# shift_relays.net
KiCad netlist of a schematic drawn in Altium Designer
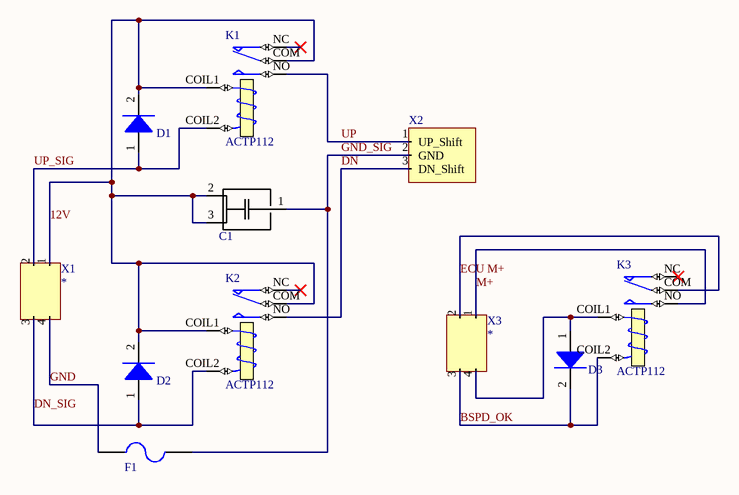
[diagram p0: shift_relays.SchDoc]

(export (version "E")
  (design (tool "Eeschema 10.0.6"))
  (components
    (comp (ref "C1")
      (value "Part Number: BZ05FB682ZSB")
      (footprint "BZX5-S")
      (description "6.8mF (EDLC) Supercapacitor 15V BZ05, 3 Lead")
      (fields
        (field (name "MANUFACTURER_PART_NUMBER") "BZ05FB682ZSB")
        (field (name "VOLTAGE") "15")
        (field (name "COPYRIGHT") "Copyright (C) 2018 Accelerated Designs. All rights reserved")
        (field (name "CREATEDBY") "Patrick Reedy")
      )
      (libsource (lib "altlib") (part "BZ05FB682ZSB"))
    )
    (comp (ref "D1")
      (value "*")
      (footprint "SOD123F")
      (description "Diode Super Barrier 40V 1A Surface Mount SOD-")
      (libsource (lib "altlib") (part "DIODE"))
    )
    (comp (ref "D2")
      (value "*")
      (footprint "SOD123F")
      (description "Diode Super Barrier 40V 1A Surface Mount SOD-")
      (libsource (lib "altlib") (part "DIODE"))
    )
    (comp (ref "D3")
      (value "*")
      (footprint "SOD123F")
      (description "Diode Super Barrier 40V 1A Surface Mount SOD-")
      (libsource (lib "altlib") (part "DIODE"))
    )
    (comp (ref "F1")
      (value "Fuse")
      (footprint "3568-MiniFuseHolder")
      (libsource (lib "altlib") (part "Fuse"))
    )
    (comp (ref "K1")
      (value "ACTP112")
      (footprint "ACTP112")
      (fields
        (field (name "VOLTAGE") "12")
        (field (name "PUBLISHER") "Altium Limited")
        (field (name "CREATEDBY") "Kevin")
      )
      (libsource (lib "altlib") (part "ACTP112"))
    )
    (comp (ref "K2")
      (value "ACTP112")
      (footprint "ACTP112")
      (fields
        (field (name "VOLTAGE") "12")
        (field (name "PUBLISHER") "Altium Limited")
        (field (name "CREATEDBY") "Kevin")
      )
      (libsource (lib "altlib") (part "ACTP112"))
    )
    (comp (ref "K3")
      (value "ACTP112")
      (footprint "ACTP112")
      (fields
        (field (name "VOLTAGE") "12")
        (field (name "PUBLISHER") "Altium Limited")
        (field (name "CREATEDBY") "Kevin")
      )
      (libsource (lib "altlib") (part "ACTP112"))
    )
    (comp (ref "X1")
      (value "*")
      (footprint "DTF13-4P")
      (description "DTF13-4P")
      (libsource (lib "altlib") (part "CONN 4POS"))
    )
    (comp (ref "X2")
      (value "~")
      (footprint "CONN_Shift")
      (description "Connector for Shift Relays")
      (fields (field (name "CREATEDBY") "Patrick"))
      (libsource (lib "altlib") (part "CONN Shift"))
    )
    (comp (ref "X3")
      (value "*")
      (footprint "DTF13-4P")
      (description "DTF13-4P")
      (libsource (lib "altlib") (part "CONN 4POS"))
    )
  )
  (nets
    (net (code "1") (name "/12V") (class "Default")
      (node (ref "C1") (pin "2") (pinfunction "2_2") (pintype "passive"))
      (node (ref "C1") (pin "3") (pinfunction "3_3") (pintype "passive"))
      (node (ref "D1") (pin "2") (pinfunction "K_2") (pintype "passive"))
      (node (ref "D2") (pin "2") (pinfunction "K_2") (pintype "passive"))
      (node (ref "K1") (pin "COIL1") (pinfunction "T1_COIL1") (pintype "bidirectional"))
      (node (ref "K1") (pin "COM") (pinfunction "COM_COM") (pintype "bidirectional"))
      (node (ref "K2") (pin "COIL1") (pinfunction "T1_COIL1") (pintype "bidirectional"))
      (node (ref "K2") (pin "COM") (pinfunction "COM_COM") (pintype "bidirectional"))
      (node (ref "X1") (pin "1") (pintype "input"))
    )
    (net (code "2") (name "/BSPD_OK") (class "Default")
      (node (ref "D3") (pin "2") (pinfunction "K_2") (pintype "passive"))
      (node (ref "K3") (pin "COIL2") (pinfunction "T2_COIL2") (pintype "bidirectional"))
      (node (ref "X3") (pin "3") (pintype "input"))
    )
    (net (code "3") (name "/DN") (class "Default")
      (node (ref "K2") (pin "NO") (pinfunction "NO_NO") (pintype "bidirectional"))
      (node (ref "X2") (pin "3") (pinfunction "DN_Shift_3") (pintype "input"))
    )
    (net (code "4") (name "/DN_SIG") (class "Default")
      (node (ref "D2") (pin "1") (pinfunction "A_1") (pintype "passive"))
      (node (ref "K2") (pin "COIL2") (pinfunction "T2_COIL2") (pintype "bidirectional"))
      (node (ref "X1") (pin "3") (pintype "input"))
    )
    (net (code "5") (name "/ECU M+") (class "Default")
      (node (ref "K3") (pin "COM") (pinfunction "COM_COM") (pintype "bidirectional"))
      (node (ref "X3") (pin "2") (pintype "input"))
    )
    (net (code "6") (name "/GND") (class "Default")
      (node (ref "F1") (pin "1") (pinfunction "1_1") (pintype "passive"))
      (node (ref "X1") (pin "4") (pintype "input"))
    )
    (net (code "7") (name "/GND_SIG") (class "Default")
      (node (ref "C1") (pin "1") (pinfunction "1_1") (pintype "passive"))
      (node (ref "F1") (pin "2") (pinfunction "2_2") (pintype "passive"))
      (node (ref "X2") (pin "2") (pinfunction "GND_2") (pintype "input"))
    )
    (net (code "8") (name "/M+") (class "Default")
      (node (ref "K3") (pin "NO") (pinfunction "NO_NO") (pintype "bidirectional"))
      (node (ref "X3") (pin "1") (pintype "input"))
    )
    (net (code "9") (name "/UP") (class "Default")
      (node (ref "K1") (pin "NO") (pinfunction "NO_NO") (pintype "bidirectional"))
      (node (ref "X2") (pin "1") (pinfunction "UP_Shift_1") (pintype "input"))
    )
    (net (code "10") (name "/UP_SIG") (class "Default")
      (node (ref "D1") (pin "1") (pinfunction "A_1") (pintype "passive"))
      (node (ref "K1") (pin "COIL2") (pinfunction "T2_COIL2") (pintype "bidirectional"))
      (node (ref "X1") (pin "2") (pintype "input"))
    )
    (net (code "11") (name "Net-(D3-A)") (class "Default")
      (node (ref "D3") (pin "1") (pinfunction "A_1") (pintype "passive"))
      (node (ref "K3") (pin "COIL1") (pinfunction "T1_COIL1") (pintype "bidirectional"))
      (node (ref "X3") (pin "4") (pintype "input"))
    )
    (net (code "12") (name "unconnected-(K1-PadNC)") (class "Default")
      (node (ref "K1") (pin "NC") (pinfunction "NC_NC") (pintype "bidirectional+no_connect"))
    )
    (net (code "13") (name "unconnected-(K2-PadNC)") (class "Default")
      (node (ref "K2") (pin "NC") (pinfunction "NC_NC") (pintype "bidirectional+no_connect"))
    )
    (net (code "14") (name "unconnected-(K3-PadNC)") (class "Default")
      (node (ref "K3") (pin "NC") (pinfunction "NC_NC") (pintype "bidirectional+no_connect"))
    )
  )
)
